# PANEL_2.net
KiCad netlist of a schematic drawn in EAGLE
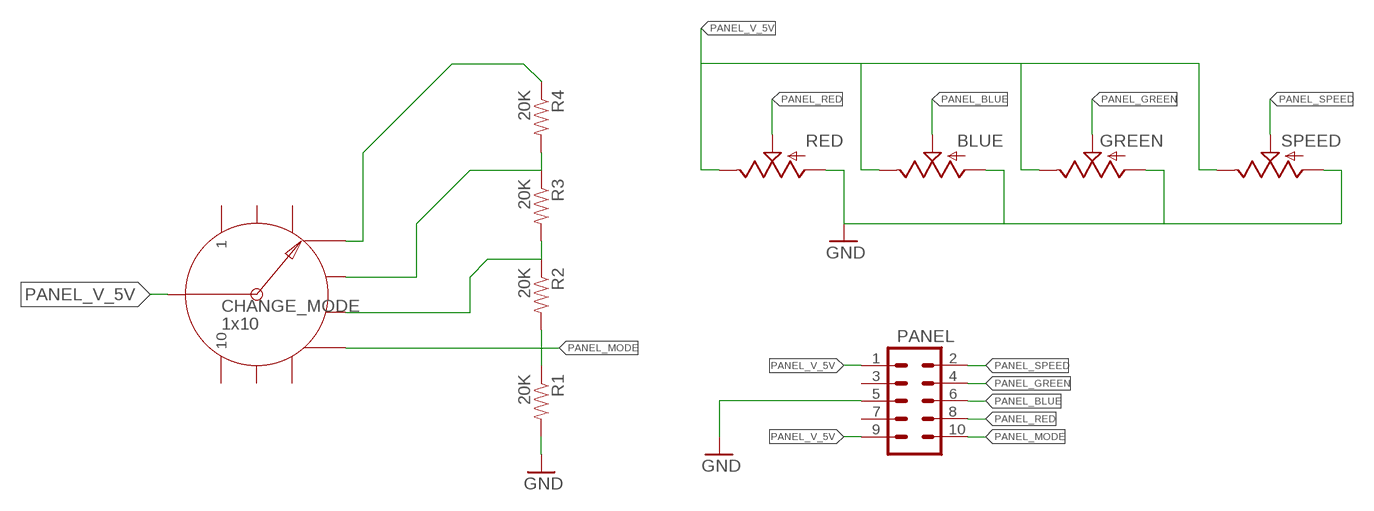
[diagram p0: schematic, sheet 1]

(export (version "E")
  (design (tool "Eeschema 10.0.6"))
  (components
    (comp (ref "BLUE")
      (value "POT-RV16AF-20")
      (footprint "eagle-import:POT_ALPHA_RV16AF-20")
      (libsource (lib "eagle-import") (part "POT-RV16AF-20"))
    )
    (comp (ref "CHANGE_MODE")
      (value "1x10")
      (footprint "eagle-import:ROTARY_SWITCH_1X10")
      (libsource (lib "eagle-import") (part "SWITCH_ROTARY_1X10"))
    )
    (comp (ref "GREEN")
      (value "POT-RV16AF-20")
      (footprint "eagle-import:POT_ALPHA_RV16AF-20")
      (libsource (lib "eagle-import") (part "POT-RV16AF-20"))
    )
    (comp (ref "PANEL")
      (value "M05X2SHD")
      (footprint "eagle-import:2X5-SHROUDED")
      (libsource (lib "eagle-import") (part "M05X2SHD"))
    )
    (comp (ref "R1")
      (value "20K")
      (footprint "eagle-import:AXIAL-0.3EZ")
      (libsource (lib "eagle-import") (part "RESISTOREZ"))
    )
    (comp (ref "R2")
      (value "20K")
      (footprint "eagle-import:AXIAL-0.3EZ")
      (libsource (lib "eagle-import") (part "RESISTOREZ"))
    )
    (comp (ref "R3")
      (value "20K")
      (footprint "eagle-import:AXIAL-0.3EZ")
      (libsource (lib "eagle-import") (part "RESISTOREZ"))
    )
    (comp (ref "R4")
      (value "20K")
      (footprint "eagle-import:AXIAL-0.3EZ")
      (libsource (lib "eagle-import") (part "RESISTOREZ"))
    )
    (comp (ref "RED")
      (value "POT-RV16AF-20")
      (footprint "eagle-import:POT_ALPHA_RV16AF-20")
      (libsource (lib "eagle-import") (part "POT-RV16AF-20"))
    )
    (comp (ref "SPEED")
      (value "POT-RV16AF-20")
      (footprint "eagle-import:POT_ALPHA_RV16AF-20")
      (libsource (lib "eagle-import") (part "POT-RV16AF-20"))
    )
  )
  (nets
    (net (code "1") (name "GND") (class "Default")
      (node (ref "BLUE") (pin "1") (pinfunction "A_1") (pintype "passive"))
      (node (ref "GREEN") (pin "1") (pinfunction "A_1") (pintype "passive"))
      (node (ref "PANEL") (pin "5") (pinfunction "5_5") (pintype "passive"))
      (node (ref "R1") (pin "P$2") (pinfunction "2_P$2") (pintype "passive"))
      (node (ref "RED") (pin "1") (pinfunction "A_1") (pintype "passive"))
      (node (ref "SPEED") (pin "1") (pinfunction "A_1") (pintype "passive"))
    )
    (net (code "2") (name "Net-(R2-1)") (class "Default")
      (node (ref "CHANGE_MODE") (pin "6") (pinfunction "6_6") (pintype "bidirectional"))
      (node (ref "R2") (pin "P$1") (pinfunction "1_P$1") (pintype "passive"))
      (node (ref "R3") (pin "P$2") (pinfunction "2_P$2") (pintype "passive"))
    )
    (net (code "3") (name "Net-(R3-1)") (class "Default")
      (node (ref "CHANGE_MODE") (pin "5") (pinfunction "5_5") (pintype "bidirectional"))
      (node (ref "R3") (pin "P$1") (pinfunction "1_P$1") (pintype "passive"))
      (node (ref "R4") (pin "P$2") (pinfunction "2_P$2") (pintype "passive"))
    )
    (net (code "4") (name "Net-(R4-1)") (class "Default")
      (node (ref "CHANGE_MODE") (pin "4") (pinfunction "4_4") (pintype "bidirectional"))
      (node (ref "R4") (pin "P$1") (pinfunction "1_P$1") (pintype "passive"))
    )
    (net (code "5") (name "PANEL_BLUE") (class "Default")
      (node (ref "BLUE") (pin "2") (pinfunction "S_2") (pintype "passive"))
      (node (ref "PANEL") (pin "6") (pinfunction "6_6") (pintype "passive"))
    )
    (net (code "6") (name "PANEL_GREEN") (class "Default")
      (node (ref "GREEN") (pin "2") (pinfunction "S_2") (pintype "passive"))
      (node (ref "PANEL") (pin "4") (pinfunction "4_4") (pintype "passive"))
    )
    (net (code "7") (name "PANEL_MODE") (class "Default")
      (node (ref "CHANGE_MODE") (pin "7") (pinfunction "7_7") (pintype "bidirectional"))
      (node (ref "PANEL") (pin "10") (pinfunction "10_10") (pintype "passive"))
      (node (ref "R1") (pin "P$1") (pinfunction "1_P$1") (pintype "passive"))
      (node (ref "R2") (pin "P$2") (pinfunction "2_P$2") (pintype "passive"))
    )
    (net (code "8") (name "PANEL_RED") (class "Default")
      (node (ref "PANEL") (pin "8") (pinfunction "8_8") (pintype "passive"))
      (node (ref "RED") (pin "2") (pinfunction "S_2") (pintype "passive"))
    )
    (net (code "9") (name "PANEL_SPEED") (class "Default")
      (node (ref "PANEL") (pin "2") (pinfunction "2_2") (pintype "passive"))
      (node (ref "SPEED") (pin "2") (pinfunction "S_2") (pintype "passive"))
    )
    (net (code "10") (name "PANEL_V_5V") (class "Default")
      (node (ref "BLUE") (pin "3") (pinfunction "E_3") (pintype "passive"))
      (node (ref "CHANGE_MODE") (pin "COMMON") (pinfunction "COMMON_COMMON") (pintype "bidirectional"))
      (node (ref "GREEN") (pin "3") (pinfunction "E_3") (pintype "passive"))
      (node (ref "PANEL") (pin "1") (pinfunction "1_1") (pintype "passive"))
      (node (ref "PANEL") (pin "9") (pinfunction "9_9") (pintype "passive"))
      (node (ref "RED") (pin "3") (pinfunction "E_3") (pintype "passive"))
      (node (ref "SPEED") (pin "3") (pinfunction "E_3") (pintype "passive"))
    )
    (net (code "11") (name "unconnected-(CHANGE_MODE-Pad1)") (class "Default")
      (node (ref "CHANGE_MODE") (pin "1") (pinfunction "1_1") (pintype "bidirectional"))
    )
    (net (code "12") (name "unconnected-(CHANGE_MODE-Pad2)") (class "Default")
      (node (ref "CHANGE_MODE") (pin "2") (pinfunction "2_2") (pintype "bidirectional"))
    )
    (net (code "13") (name "unconnected-(CHANGE_MODE-Pad3)") (class "Default")
      (node (ref "CHANGE_MODE") (pin "3") (pinfunction "3_3") (pintype "bidirectional"))
    )
    (net (code "14") (name "unconnected-(CHANGE_MODE-Pad8)") (class "Default")
      (node (ref "CHANGE_MODE") (pin "8") (pinfunction "8_8") (pintype "bidirectional"))
    )
    (net (code "15") (name "unconnected-(CHANGE_MODE-Pad9)") (class "Default")
      (node (ref "CHANGE_MODE") (pin "9") (pinfunction "9_9") (pintype "bidirectional"))
    )
    (net (code "16") (name "unconnected-(CHANGE_MODE-Pad10)") (class "Default")
      (node (ref "CHANGE_MODE") (pin "10") (pinfunction "10_10") (pintype "bidirectional"))
    )
    (net (code "17") (name "unconnected-(PANEL-Pad3)") (class "Default")
      (node (ref "PANEL") (pin "3") (pinfunction "3_3") (pintype "passive"))
    )
    (net (code "18") (name "unconnected-(PANEL-Pad7)") (class "Default")
      (node (ref "PANEL") (pin "7") (pinfunction "7_7") (pintype "passive"))
    )
  )
)
